# HW2_Micro2.net
KiCad netlist of a schematic drawn in EAGLE
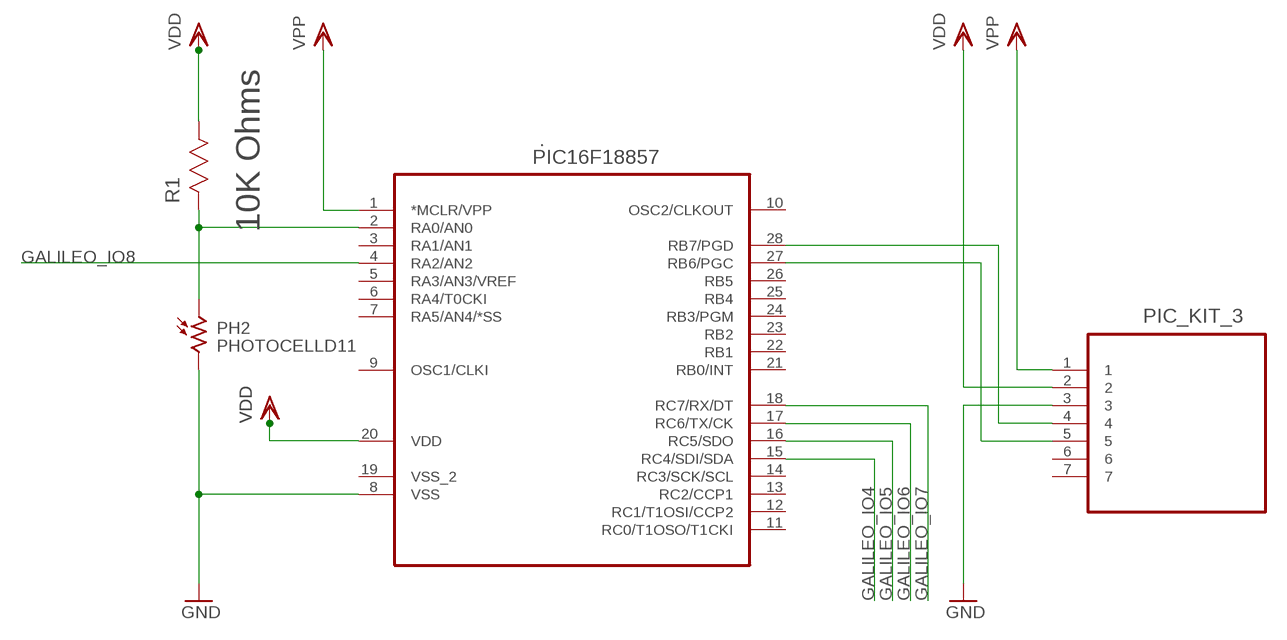
[diagram p0: schematic, sheet 1]

(export (version "E")
  (design (tool "Eeschema 10.0.6"))
  (components
    (comp (ref ".")
      (value "PIC16F18857")
      (footprint "eagle-import:DIP254P724X406-28")
      (fields (field (name "MPN") "PIC16LF76-I/SP"))
      (libsource (lib "eagle-import") (part "PIC16LF76-I/SP"))
    )
    (comp (ref "PH2")
      (value "PHOTOCELLD11")
      (footprint "eagle-import:D11XX_H")
      (libsource (lib "eagle-import") (part "PHOTOCELLD11"))
    )
    (comp (ref "PIC_KIT_3")
      (value "TLW-107-06-T-S")
      (footprint "eagle-import:SAMTEC_TLW-107-06-T-S")
      (libsource (lib "eagle-import") (part "TLW-107-06-T-S"))
    )
    (comp (ref "R1")
      (value "10K Ohms")
      (footprint "eagle-import:RESC1608X60N")
      (fields (field (name "MPN") "CRCW060312K4FKEA") (field (name "TOLERANCE") "± 1.0 %"))
      (libsource (lib "eagle-import") (part "CRCW060312K4FKEA"))
    )
  )
  (nets
    (net (code "1") (name "/GALILEO_IO4") (class "Default")
      (node (ref ".") (pin "15") (pinfunction "RC4/SDI/SDA_15") (pintype "bidirectional"))
    )
    (net (code "2") (name "/GALILEO_IO5") (class "Default")
      (node (ref ".") (pin "16") (pinfunction "RC5/SDO_16") (pintype "bidirectional"))
    )
    (net (code "3") (name "/GALILEO_IO6") (class "Default")
      (node (ref ".") (pin "17") (pinfunction "RC6/TX/CK_17") (pintype "bidirectional"))
    )
    (net (code "4") (name "/GALILEO_IO7") (class "Default")
      (node (ref ".") (pin "18") (pinfunction "RC7/RX/DT_18") (pintype "bidirectional"))
    )
    (net (code "5") (name "/GALILEO_IO8") (class "Default")
      (node (ref ".") (pin "4") (pinfunction "RA2/AN2_4") (pintype "bidirectional"))
    )
    (net (code "6") (name "GND") (class "Default")
      (node (ref ".") (pin "8") (pinfunction "VSS_8") (pintype "passive"))
      (node (ref "PH2") (pin "2") (pinfunction "2_2") (pintype "passive"))
      (node (ref "PIC_KIT_3") (pin "3") (pinfunction "3_3") (pintype "passive"))
    )
    (net (code "7") (name "Net-(.-RA0{slash}AN0)") (class "Default")
      (node (ref ".") (pin "2") (pinfunction "RA0/AN0_2") (pintype "bidirectional"))
      (node (ref "PH2") (pin "1") (pinfunction "1_1") (pintype "passive"))
      (node (ref "R1") (pin "2") (pinfunction "2_2") (pintype "passive"))
    )
    (net (code "8") (name "Net-(.-RB6{slash}PGC)") (class "Default")
      (node (ref ".") (pin "27") (pinfunction "RB6/PGC_27") (pintype "bidirectional"))
      (node (ref "PIC_KIT_3") (pin "5") (pinfunction "5_5") (pintype "passive"))
    )
    (net (code "9") (name "Net-(.-RB7{slash}PGD)") (class "Default")
      (node (ref ".") (pin "28") (pinfunction "RB7/PGD_28") (pintype "bidirectional"))
      (node (ref "PIC_KIT_3") (pin "4") (pinfunction "4_4") (pintype "passive"))
    )
    (net (code "10") (name "VDD") (class "Default")
      (node (ref ".") (pin "1") (pinfunction "*MCLR/VPP_1") (pintype "input"))
      (node (ref ".") (pin "20") (pinfunction "VDD_20") (pintype "power_in"))
      (node (ref "PIC_KIT_3") (pin "1") (pinfunction "1_1") (pintype "passive"))
      (node (ref "PIC_KIT_3") (pin "2") (pinfunction "2_2") (pintype "passive"))
      (node (ref "R1") (pin "1") (pinfunction "1_1") (pintype "passive"))
    )
    (net (code "11") (name "unconnected-(.-OSC1{slash}CLKI-Pad9)") (class "Default")
      (node (ref ".") (pin "9") (pinfunction "OSC1/CLKI_9") (pintype "input"))
    )
    (net (code "12") (name "unconnected-(.-OSC2{slash}CLKOUT-Pad10)") (class "Default")
      (node (ref ".") (pin "10") (pinfunction "OSC2/CLKOUT_10") (pintype "output"))
    )
    (net (code "13") (name "unconnected-(.-RA1{slash}AN1-Pad3)") (class "Default")
      (node (ref ".") (pin "3") (pinfunction "RA1/AN1_3") (pintype "bidirectional"))
    )
    (net (code "14") (name "unconnected-(.-RA3{slash}AN3{slash}VREF-Pad5)") (class "Default")
      (node (ref ".") (pin "5") (pinfunction "RA3/AN3/VREF_5") (pintype "bidirectional"))
    )
    (net (code "15") (name "unconnected-(.-RA4{slash}T0CKI-Pad6)") (class "Default")
      (node (ref ".") (pin "6") (pinfunction "RA4/T0CKI_6") (pintype "bidirectional"))
    )
    (net (code "16") (name "unconnected-(.-RA5{slash}AN4{slash}*SS-Pad7)") (class "Default")
      (node (ref ".") (pin "7") (pinfunction "RA5/AN4/*SS_7") (pintype "bidirectional"))
    )
    (net (code "17") (name "unconnected-(.-RB0{slash}INT-Pad21)") (class "Default")
      (node (ref ".") (pin "21") (pinfunction "RB0/INT_21") (pintype "bidirectional"))
    )
    (net (code "18") (name "unconnected-(.-RB1-Pad22)") (class "Default")
      (node (ref ".") (pin "22") (pinfunction "RB1_22") (pintype "bidirectional"))
    )
    (net (code "19") (name "unconnected-(.-RB2-Pad23)") (class "Default")
      (node (ref ".") (pin "23") (pinfunction "RB2_23") (pintype "bidirectional"))
    )
    (net (code "20") (name "unconnected-(.-RB3{slash}PGM-Pad24)") (class "Default")
      (node (ref ".") (pin "24") (pinfunction "RB3/PGM_24") (pintype "bidirectional"))
    )
    (net (code "21") (name "unconnected-(.-RB4-Pad25)") (class "Default")
      (node (ref ".") (pin "25") (pinfunction "RB4_25") (pintype "bidirectional"))
    )
    (net (code "22") (name "unconnected-(.-RB5-Pad26)") (class "Default")
      (node (ref ".") (pin "26") (pinfunction "RB5_26") (pintype "bidirectional"))
    )
    (net (code "23") (name "unconnected-(.-RC0{slash}T1OSO{slash}T1CKI-Pad11)") (class "Default")
      (node (ref ".") (pin "11") (pinfunction "RC0/T1OSO/T1CKI_11") (pintype "bidirectional"))
    )
    (net (code "24") (name "unconnected-(.-RC1{slash}T1OSI{slash}CCP2-Pad12)") (class "Default")
      (node (ref ".") (pin "12") (pinfunction "RC1/T1OSI/CCP2_12") (pintype "bidirectional"))
    )
    (net (code "25") (name "unconnected-(.-RC2{slash}CCP1-Pad13)") (class "Default")
      (node (ref ".") (pin "13") (pinfunction "RC2/CCP1_13") (pintype "bidirectional"))
    )
    (net (code "26") (name "unconnected-(.-RC3{slash}SCK{slash}SCL-Pad14)") (class "Default")
      (node (ref ".") (pin "14") (pinfunction "RC3/SCK/SCL_14") (pintype "bidirectional"))
    )
    (net (code "27") (name "unconnected-(.-VSS_2-Pad19)") (class "Default")
      (node (ref ".") (pin "19") (pinfunction "VSS_2_19") (pintype "passive"))
    )
    (net (code "28") (name "unconnected-(PIC_KIT_3-Pad6)") (class "Default")
      (node (ref "PIC_KIT_3") (pin "6") (pinfunction "6_6") (pintype "passive"))
    )
    (net (code "29") (name "unconnected-(PIC_KIT_3-Pad7)") (class "Default")
      (node (ref "PIC_KIT_3") (pin "7") (pinfunction "7_7") (pintype "passive"))
    )
  )
)
